# UWB-Breakout.net
KiCad netlist of a schematic drawn in EAGLE
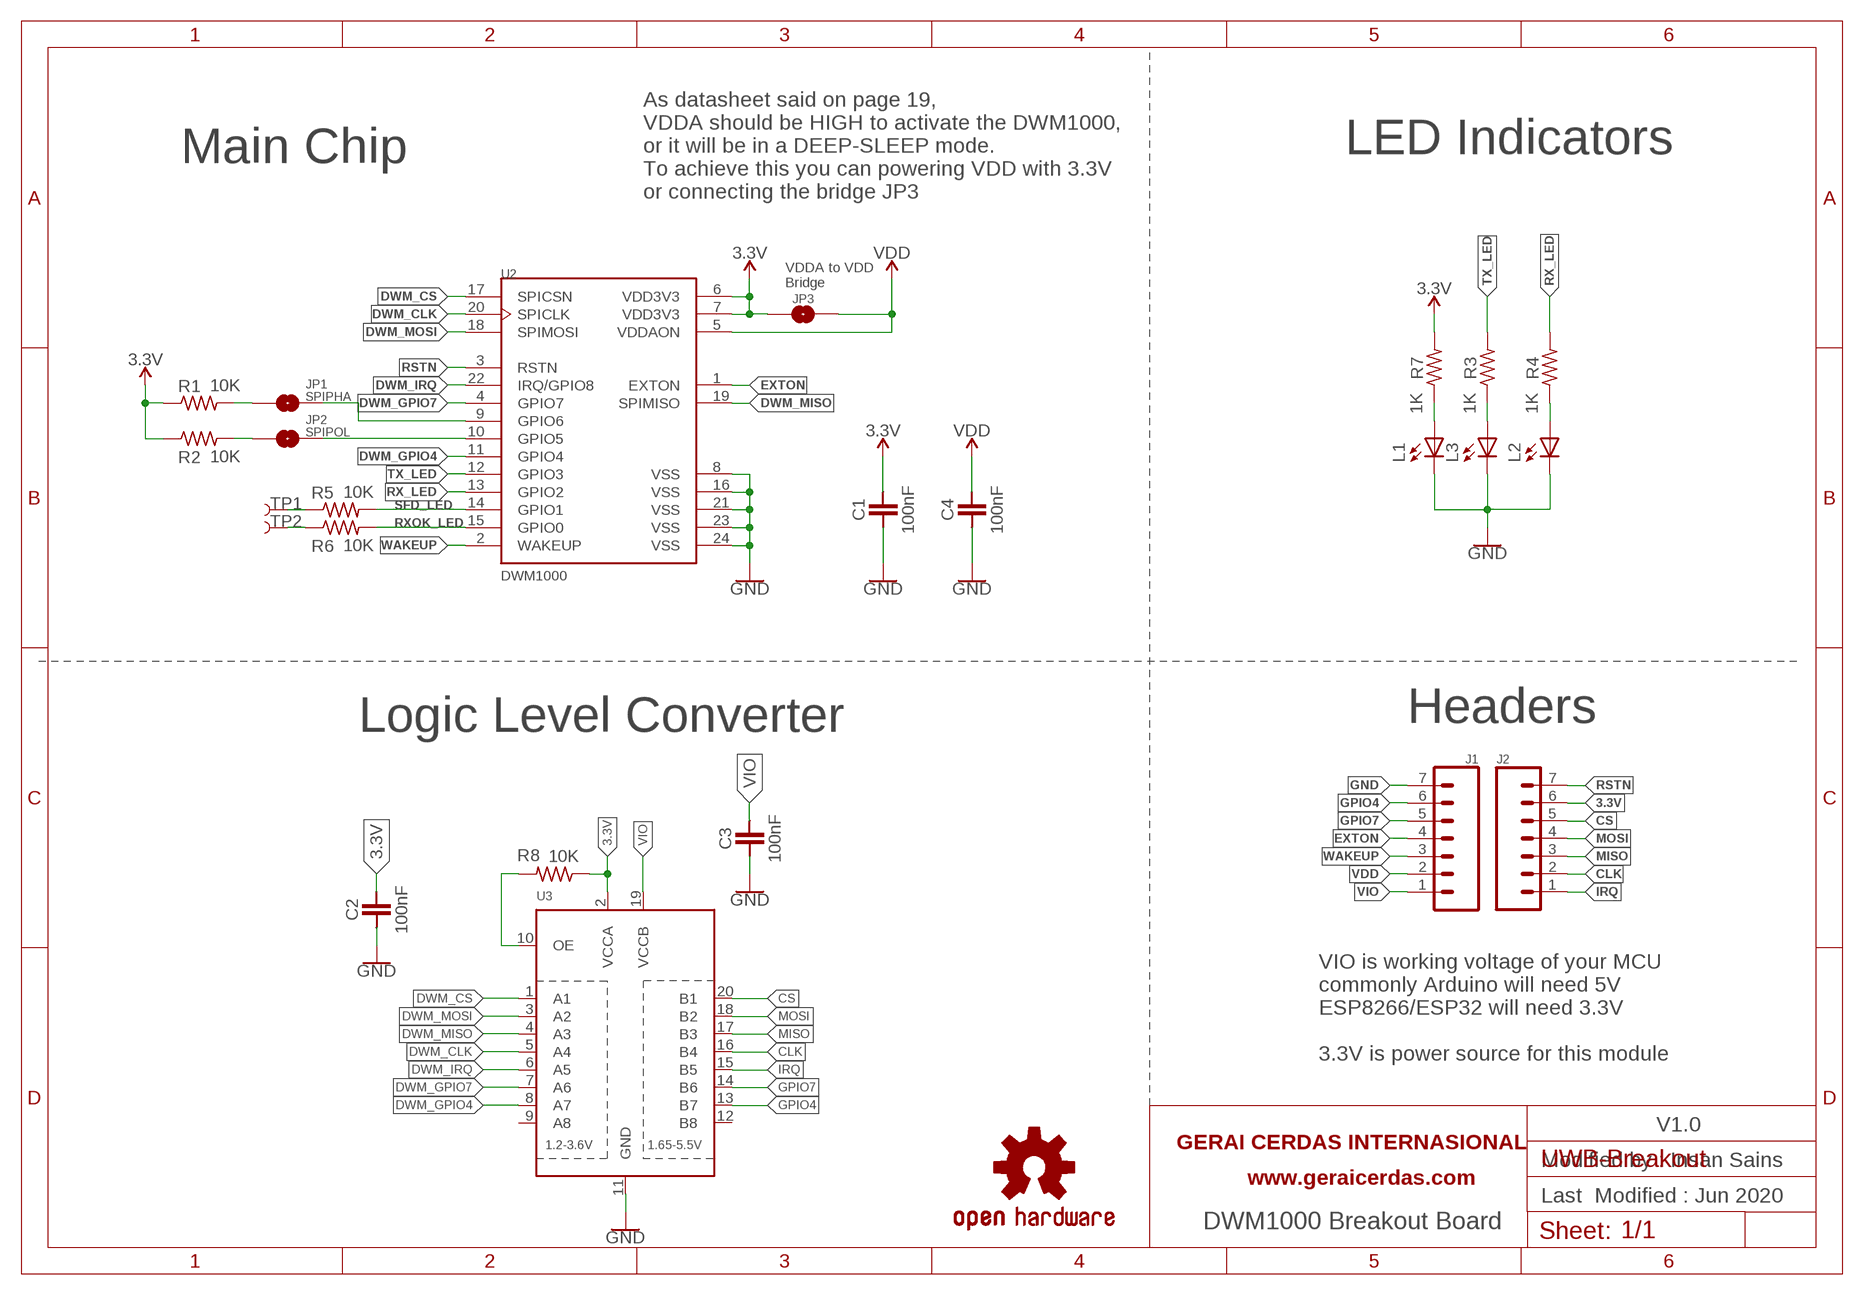
[diagram p0: schematic, sheet 1]

(export (version "E")
  (design (tool "Eeschema 10.0.6"))
  (components
    (comp (ref "C1")
      (value "100nF")
      (footprint "eagle-import:C0603")
      (libsource (lib "eagle-import") (part "CAPACITOR-SMD0603"))
    )
    (comp (ref "C2")
      (value "100nF")
      (footprint "eagle-import:C0603")
      (libsource (lib "eagle-import") (part "CAPACITOR-SMD0603"))
    )
    (comp (ref "C3")
      (value "100nF")
      (footprint "eagle-import:C0603")
      (libsource (lib "eagle-import") (part "CAPACITOR-SMD0603"))
    )
    (comp (ref "C4")
      (value "100nF")
      (footprint "eagle-import:C0603")
      (libsource (lib "eagle-import") (part "CAPACITOR-SMD0603"))
    )
    (comp (ref "FRAME1")
      (value "FRAME")
      (footprint "eagle-import:A4-HOR")
      (libsource (lib "eagle-import") (part "FRAME"))
    )
    (comp (ref "J1")
      (value "CONN_07NO_SILK")
      (footprint "eagle-import:1X07_NO_SILK")
      (libsource (lib "eagle-import") (part "CONN_07NO_SILK"))
    )
    (comp (ref "J2")
      (value "CONN_07NO_SILK")
      (footprint "eagle-import:1X07_NO_SILK")
      (libsource (lib "eagle-import") (part "CONN_07NO_SILK"))
    )
    (comp (ref "JP1")
      (value "SPIPHA")
      (footprint "eagle-import:SMT-JUMPER_2_NO_SILK")
      (libsource (lib "eagle-import") (part "JUMPER-SMT_2_NO_SILK"))
    )
    (comp (ref "JP2")
      (value "SPIPOL")
      (footprint "eagle-import:SMT-JUMPER_2_NO_SILK")
      (libsource (lib "eagle-import") (part "JUMPER-SMT_2_NO_SILK"))
    )
    (comp (ref "JP3")
      (value "JUMPER-SMT_2_NO_SILK")
      (footprint "eagle-import:SMT-JUMPER_2_NO_SILK")
      (libsource (lib "eagle-import") (part "JUMPER-SMT_2_NO_SILK"))
    )
    (comp (ref "L1")
      (value "LED-SMD0805")
      (footprint "eagle-import:LED0805")
      (libsource (lib "eagle-import") (part "LED-SMD0805"))
    )
    (comp (ref "L2")
      (value "LED-SMD0805")
      (footprint "eagle-import:LED0805")
      (libsource (lib "eagle-import") (part "LED-SMD0805"))
    )
    (comp (ref "L3")
      (value "LED-SMD0805")
      (footprint "eagle-import:LED0805")
      (libsource (lib "eagle-import") (part "LED-SMD0805"))
    )
    (comp (ref "LOGO1")
      (value "OSHW-LOGOM")
      (footprint "eagle-import:OSHW-LOGO-M")
      (libsource (lib "eagle-import") (part "OSHW-LOGOM"))
    )
    (comp (ref "R1")
      (value "10K")
      (footprint "eagle-import:R0603")
      (libsource (lib "eagle-import") (part "RESISTOR-SMD0603"))
    )
    (comp (ref "R2")
      (value "10K")
      (footprint "eagle-import:R0603")
      (libsource (lib "eagle-import") (part "RESISTOR-SMD0603"))
    )
    (comp (ref "R3")
      (value "1K")
      (footprint "eagle-import:R0603")
      (libsource (lib "eagle-import") (part "RESISTOR-SMD0603"))
    )
    (comp (ref "R4")
      (value "1K")
      (footprint "eagle-import:R0603")
      (libsource (lib "eagle-import") (part "RESISTOR-SMD0603"))
    )
    (comp (ref "R5")
      (value "10K")
      (footprint "eagle-import:R0603")
      (libsource (lib "eagle-import") (part "RESISTOR-SMD0603"))
    )
    (comp (ref "R6")
      (value "10K")
      (footprint "eagle-import:R0603")
      (libsource (lib "eagle-import") (part "RESISTOR-SMD0603"))
    )
    (comp (ref "R7")
      (value "1K")
      (footprint "eagle-import:R0603")
      (libsource (lib "eagle-import") (part "RESISTOR-SMD0603"))
    )
    (comp (ref "R8")
      (value "10K")
      (footprint "eagle-import:R0603")
      (libsource (lib "eagle-import") (part "RESISTOR-SMD0603"))
    )
    (comp (ref "TP1")
      (value "TEST-POINT3X5")
      (footprint "eagle-import:PAD.03X.05")
      (libsource (lib "eagle-import") (part "TEST-POINT3X5"))
    )
    (comp (ref "TP2")
      (value "TEST-POINT3X5")
      (footprint "eagle-import:PAD.03X.05")
      (libsource (lib "eagle-import") (part "TEST-POINT3X5"))
    )
    (comp (ref "U2")
      (value "DWM1000")
      (footprint "eagle-import:XCVR_DWM1000")
      (fields (field (name "MF") "Decawave Limited"))
      (libsource (lib "eagle-import") (part "DWM1000"))
    )
    (comp (ref "U3")
      (value "TXB0108PWR")
      (footprint "eagle-import:TSSOP20")
      (libsource (lib "eagle-import") (part "TXB0108PWR"))
    )
  )
  (nets
    (net (code "1") (name "/RXOK_LED") (class "Default")
      (node (ref "R6") (pin "2") (pinfunction "2_2") (pintype "passive"))
      (node (ref "U2") (pin "15") (pinfunction "GPIO0_15") (pintype "bidirectional"))
    )
    (net (code "2") (name "/SFD_LED") (class "Default")
      (node (ref "R5") (pin "2") (pinfunction "2_2") (pintype "passive"))
      (node (ref "U2") (pin "14") (pinfunction "GPIO1_14") (pintype "bidirectional"))
    )
    (net (code "3") (name "3.3V") (class "Default")
      (node (ref "C1") (pin "2") (pinfunction "2_2") (pintype "passive"))
      (node (ref "C2") (pin "2") (pinfunction "2_2") (pintype "passive"))
      (node (ref "J2") (pin "6") (pinfunction "6_6") (pintype "passive"))
      (node (ref "JP3") (pin "1") (pinfunction "1_1") (pintype "passive"))
      (node (ref "R1") (pin "1") (pinfunction "1_1") (pintype "passive"))
      (node (ref "R2") (pin "1") (pinfunction "1_1") (pintype "passive"))
      (node (ref "R7") (pin "2") (pinfunction "2_2") (pintype "passive"))
      (node (ref "R8") (pin "1") (pinfunction "1_1") (pintype "passive"))
      (node (ref "U2") (pin "6") (pinfunction "VDD3V3_6") (pintype "power_in"))
      (node (ref "U2") (pin "7") (pinfunction "VDD3V3_7") (pintype "power_in"))
      (node (ref "U3") (pin "2") (pinfunction "VCCA_2") (pintype "bidirectional"))
    )
    (net (code "4") (name "CLK") (class "Default")
      (node (ref "J2") (pin "2") (pinfunction "2_2") (pintype "passive"))
      (node (ref "U3") (pin "16") (pinfunction "B4_16") (pintype "bidirectional"))
    )
    (net (code "5") (name "CS") (class "Default")
      (node (ref "J2") (pin "5") (pinfunction "5_5") (pintype "passive"))
      (node (ref "U3") (pin "20") (pinfunction "B1_20") (pintype "bidirectional"))
    )
    (net (code "6") (name "DWM_CLK") (class "Default")
      (node (ref "U2") (pin "20") (pinfunction "SPICLK_20") (pintype "input"))
      (node (ref "U3") (pin "5") (pinfunction "A4_5") (pintype "bidirectional"))
    )
    (net (code "7") (name "DWM_CS") (class "Default")
      (node (ref "U2") (pin "17") (pinfunction "SPICSN_17") (pintype "input"))
      (node (ref "U3") (pin "1") (pinfunction "A1_1") (pintype "bidirectional"))
    )
    (net (code "8") (name "DWM_GPIO4") (class "Default")
      (node (ref "U2") (pin "11") (pinfunction "GPIO4_11") (pintype "bidirectional"))
      (node (ref "U3") (pin "8") (pinfunction "A7_8") (pintype "bidirectional"))
    )
    (net (code "9") (name "DWM_GPIO7") (class "Default")
      (node (ref "U2") (pin "4") (pinfunction "GPIO7_4") (pintype "bidirectional"))
      (node (ref "U3") (pin "7") (pinfunction "A6_7") (pintype "bidirectional"))
    )
    (net (code "10") (name "DWM_IRQ") (class "Default")
      (node (ref "U2") (pin "22") (pinfunction "IRQ/GPIO8_22") (pintype "bidirectional"))
      (node (ref "U3") (pin "6") (pinfunction "A5_6") (pintype "bidirectional"))
    )
    (net (code "11") (name "DWM_MISO") (class "Default")
      (node (ref "U2") (pin "19") (pinfunction "SPIMISO_19") (pintype "output"))
      (node (ref "U3") (pin "4") (pinfunction "A3_4") (pintype "bidirectional"))
    )
    (net (code "12") (name "DWM_MOSI") (class "Default")
      (node (ref "U2") (pin "18") (pinfunction "SPIMOSI_18") (pintype "input"))
      (node (ref "U3") (pin "3") (pinfunction "A2_3") (pintype "bidirectional"))
    )
    (net (code "13") (name "EXTON") (class "Default")
      (node (ref "J1") (pin "4") (pinfunction "4_4") (pintype "passive"))
      (node (ref "U2") (pin "1") (pinfunction "EXTON_1") (pintype "output"))
    )
    (net (code "14") (name "GND") (class "Default")
      (node (ref "C1") (pin "1") (pinfunction "1_1") (pintype "passive"))
      (node (ref "C2") (pin "1") (pinfunction "1_1") (pintype "passive"))
      (node (ref "C3") (pin "1") (pinfunction "1_1") (pintype "passive"))
      (node (ref "C4") (pin "1") (pinfunction "1_1") (pintype "passive"))
      (node (ref "J1") (pin "7") (pinfunction "7_7") (pintype "passive"))
      (node (ref "L1") (pin "C") (pinfunction "C_C") (pintype "passive"))
      (node (ref "L2") (pin "C") (pinfunction "C_C") (pintype "passive"))
      (node (ref "L3") (pin "C") (pinfunction "C_C") (pintype "passive"))
      (node (ref "U2") (pin "16") (pinfunction "VSS_16") (pintype "power_in"))
      (node (ref "U2") (pin "21") (pinfunction "VSS_21") (pintype "power_in"))
      (node (ref "U2") (pin "23") (pinfunction "VSS_23") (pintype "power_in"))
      (node (ref "U2") (pin "24") (pinfunction "VSS_24") (pintype "power_in"))
      (node (ref "U2") (pin "8") (pinfunction "VSS_8") (pintype "power_in"))
      (node (ref "U3") (pin "11") (pinfunction "GND_11") (pintype "bidirectional"))
    )
    (net (code "15") (name "GPIO4") (class "Default")
      (node (ref "J1") (pin "6") (pinfunction "6_6") (pintype "passive"))
      (node (ref "U3") (pin "13") (pinfunction "B7_13") (pintype "bidirectional"))
    )
    (net (code "16") (name "GPIO7") (class "Default")
      (node (ref "J1") (pin "5") (pinfunction "5_5") (pintype "passive"))
      (node (ref "U3") (pin "14") (pinfunction "B6_14") (pintype "bidirectional"))
    )
    (net (code "17") (name "IRQ") (class "Default")
      (node (ref "J2") (pin "1") (pinfunction "1_1") (pintype "passive"))
      (node (ref "U3") (pin "15") (pinfunction "B5_15") (pintype "bidirectional"))
    )
    (net (code "18") (name "MISO") (class "Default")
      (node (ref "J2") (pin "3") (pinfunction "3_3") (pintype "passive"))
      (node (ref "U3") (pin "17") (pinfunction "B3_17") (pintype "bidirectional"))
    )
    (net (code "19") (name "MOSI") (class "Default")
      (node (ref "J2") (pin "4") (pinfunction "4_4") (pintype "passive"))
      (node (ref "U3") (pin "18") (pinfunction "B2_18") (pintype "bidirectional"))
    )
    (net (code "20") (name "Net-(JP1-Pad1)") (class "Default")
      (node (ref "JP1") (pin "1") (pinfunction "1_1") (pintype "passive"))
      (node (ref "R1") (pin "2") (pinfunction "2_2") (pintype "passive"))
    )
    (net (code "21") (name "Net-(JP2-Pad1)") (class "Default")
      (node (ref "JP2") (pin "1") (pinfunction "1_1") (pintype "passive"))
      (node (ref "R2") (pin "2") (pinfunction "2_2") (pintype "passive"))
    )
    (net (code "22") (name "Net-(L1-PadA)") (class "Default")
      (node (ref "L1") (pin "A") (pinfunction "A_A") (pintype "passive"))
      (node (ref "R7") (pin "1") (pinfunction "1_1") (pintype "passive"))
    )
    (net (code "23") (name "Net-(L2-PadA)") (class "Default")
      (node (ref "L2") (pin "A") (pinfunction "A_A") (pintype "passive"))
      (node (ref "R4") (pin "1") (pinfunction "1_1") (pintype "passive"))
    )
    (net (code "24") (name "Net-(L3-PadA)") (class "Default")
      (node (ref "L3") (pin "A") (pinfunction "A_A") (pintype "passive"))
      (node (ref "R3") (pin "1") (pinfunction "1_1") (pintype "passive"))
    )
    (net (code "25") (name "Net-(TP1-1)") (class "Default")
      (node (ref "R5") (pin "1") (pinfunction "1_1") (pintype "passive"))
      (node (ref "TP1") (pin "P$1") (pinfunction "1_P$1") (pintype "bidirectional"))
    )
    (net (code "26") (name "Net-(TP2-1)") (class "Default")
      (node (ref "R6") (pin "1") (pinfunction "1_1") (pintype "passive"))
      (node (ref "TP2") (pin "P$1") (pinfunction "1_P$1") (pintype "bidirectional"))
    )
    (net (code "27") (name "Net-(U2-GPIO5)") (class "Default")
      (node (ref "JP2") (pin "2") (pinfunction "2_2") (pintype "passive"))
      (node (ref "U2") (pin "10") (pinfunction "GPIO5_10") (pintype "bidirectional"))
    )
    (net (code "28") (name "Net-(U2-GPIO6)") (class "Default")
      (node (ref "JP1") (pin "2") (pinfunction "2_2") (pintype "passive"))
      (node (ref "U2") (pin "9") (pinfunction "GPIO6_9") (pintype "bidirectional"))
    )
    (net (code "29") (name "Net-(U3-OE)") (class "Default")
      (node (ref "R8") (pin "2") (pinfunction "2_2") (pintype "passive"))
      (node (ref "U3") (pin "10") (pinfunction "OE_10") (pintype "bidirectional"))
    )
    (net (code "30") (name "RSTN") (class "Default")
      (node (ref "J2") (pin "7") (pinfunction "7_7") (pintype "passive"))
      (node (ref "U2") (pin "3") (pinfunction "RSTN_3") (pintype "bidirectional"))
    )
    (net (code "31") (name "RX_LED") (class "Default")
      (node (ref "R4") (pin "2") (pinfunction "2_2") (pintype "passive"))
      (node (ref "U2") (pin "13") (pinfunction "GPIO2_13") (pintype "bidirectional"))
    )
    (net (code "32") (name "TX_LED") (class "Default")
      (node (ref "R3") (pin "2") (pinfunction "2_2") (pintype "passive"))
      (node (ref "U2") (pin "12") (pinfunction "GPIO3_12") (pintype "bidirectional"))
    )
    (net (code "33") (name "VDD") (class "Default")
      (node (ref "C4") (pin "2") (pinfunction "2_2") (pintype "passive"))
      (node (ref "J1") (pin "2") (pinfunction "2_2") (pintype "passive"))
      (node (ref "JP3") (pin "2") (pinfunction "2_2") (pintype "passive"))
      (node (ref "U2") (pin "5") (pinfunction "VDDAON_5") (pintype "power_in"))
    )
    (net (code "34") (name "VIO") (class "Default")
      (node (ref "C3") (pin "2") (pinfunction "2_2") (pintype "passive"))
      (node (ref "J1") (pin "1") (pinfunction "1_1") (pintype "passive"))
      (node (ref "U3") (pin "19") (pinfunction "VCCB_19") (pintype "bidirectional"))
    )
    (net (code "35") (name "WAKEUP") (class "Default")
      (node (ref "J1") (pin "3") (pinfunction "3_3") (pintype "passive"))
      (node (ref "U2") (pin "2") (pinfunction "WAKEUP_2") (pintype "bidirectional"))
    )
    (net (code "36") (name "unconnected-(U3-A8-Pad9)") (class "Default")
      (node (ref "U3") (pin "9") (pinfunction "A8_9") (pintype "bidirectional"))
    )
    (net (code "37") (name "unconnected-(U3-B8-Pad12)") (class "Default")
      (node (ref "U3") (pin "12") (pinfunction "B8_12") (pintype "bidirectional"))
    )
  )
)
